# RFRX.net
KiCad netlist of a schematic drawn in Altium Designer
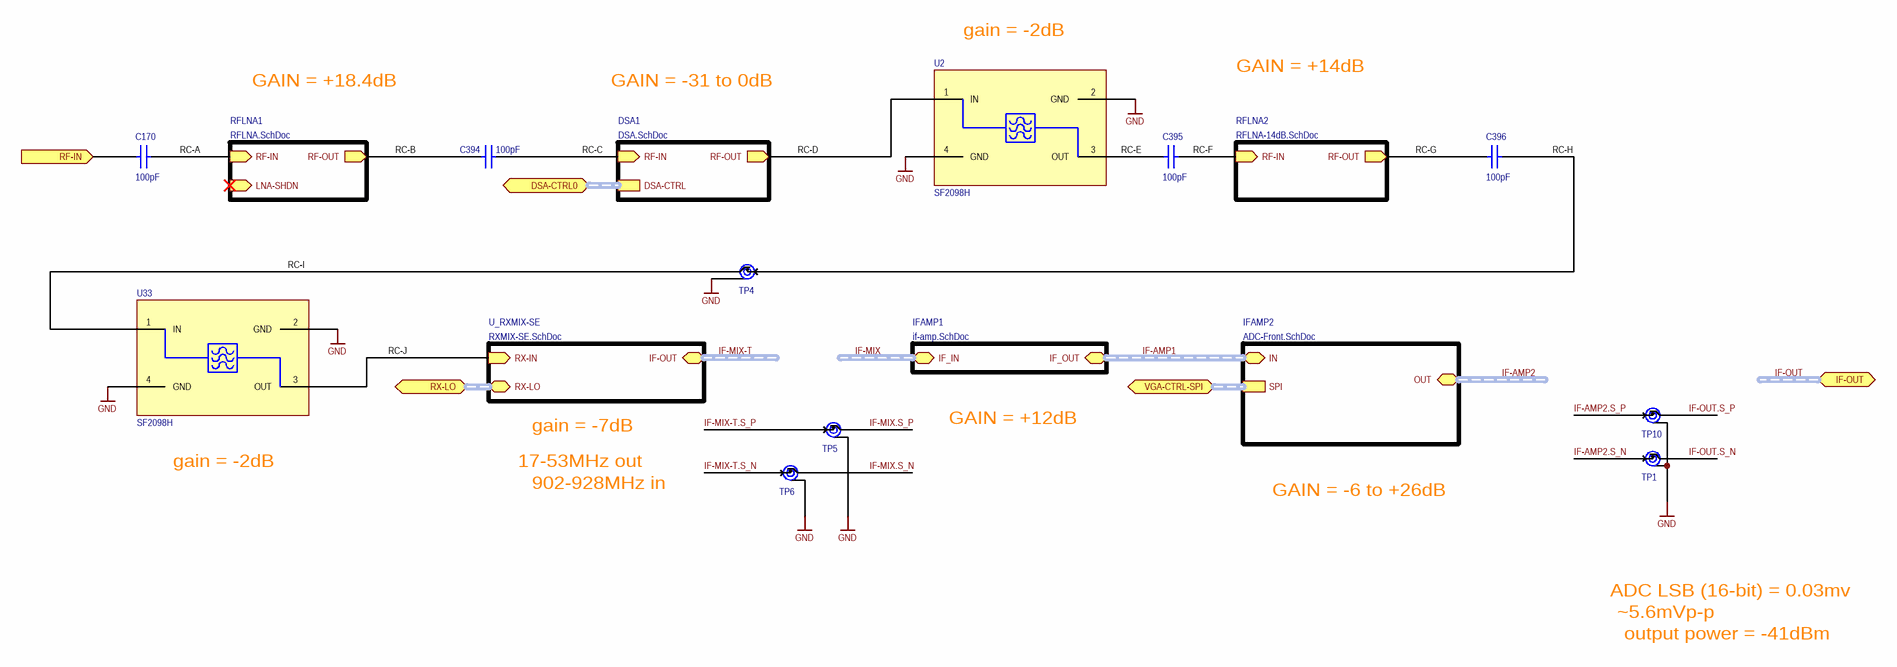
[diagram p0: RFRX.SchDoc]

(export (version "E")
  (design (tool "Eeschema 10.0.6"))
  (components
    (comp (ref "C170")
      (value "100pF")
      (footprint "0402")
      (description "Ceramic Capacitor 100pF ±1% 25V NP0 0402")
      (fields (field (name "VOLTAGE") "25V") (field (name "MANUFACTURER") "Kemet"))
      (libsource (lib "Graviton") (part "CAP 0603"))
    )
    (comp (ref "C394")
      (value "100pF")
      (footprint "0402")
      (description "Ceramic Capacitor 100pF ±1% 25V NP0 0402")
      (fields (field (name "VOLTAGE") "25V") (field (name "MANUFACTURER") "Kemet"))
      (libsource (lib "Graviton") (part "CAP 0603"))
    )
    (comp (ref "C395")
      (value "100pF")
      (footprint "0402")
      (description "Ceramic Capacitor 100pF ±1% 25V NP0 0402")
      (fields (field (name "VOLTAGE") "25V") (field (name "MANUFACTURER") "Kemet"))
      (libsource (lib "Graviton") (part "CAP 0603"))
    )
    (comp (ref "C396")
      (value "100pF")
      (footprint "0402")
      (description "Ceramic Capacitor 100pF ±1% 25V NP0 0402")
      (fields (field (name "VOLTAGE") "25V") (field (name "MANUFACTURER") "Kemet"))
      (libsource (lib "Graviton") (part "CAP 0603"))
    )
    (comp (ref "TP1")
      (value "MS-180(20)")
      (footprint "MS-180(20)")
      (description "Coaxial Connector Switch")
      (fields (field (name "MANUFACTURER") "Hirose"))
      (libsource (lib "hirose") (part "MS-180(20)"))
    )
    (comp (ref "TP4")
      (value "MS-180(20)")
      (footprint "MS-180(20)")
      (description "Coaxial Connector Switch")
      (fields (field (name "MANUFACTURER") "Hirose"))
      (libsource (lib "hirose") (part "MS-180(20)"))
    )
    (comp (ref "TP5")
      (value "MS-180(20)")
      (footprint "MS-180(20)")
      (description "Coaxial Connector Switch")
      (fields (field (name "MANUFACTURER") "Hirose"))
      (libsource (lib "hirose") (part "MS-180(20)"))
    )
    (comp (ref "TP6")
      (value "MS-180(20)")
      (footprint "MS-180(20)")
      (description "Coaxial Connector Switch")
      (fields (field (name "MANUFACTURER") "Hirose"))
      (libsource (lib "hirose") (part "MS-180(20)"))
    )
    (comp (ref "TP10")
      (value "MS-180(20)")
      (footprint "MS-180(20)")
      (description "Coaxial Connector Switch")
      (fields (field (name "MANUFACTURER") "Hirose"))
      (libsource (lib "hirose") (part "MS-180(20)"))
    )
    (comp (ref "U2")
      (value "SF2098H")
      (footprint "rfm:SM2016-4")
      (description "915 MHz SAW Filter")
      (fields (field (name "MANUFACTURER") "RFM"))
      (libsource (lib "rfm") (part "SF2098H"))
    )
    (comp (ref "U33")
      (value "SF2098H")
      (footprint "rfm:SM2016-4")
      (description "915 MHz SAW Filter")
      (fields (field (name "MANUFACTURER") "RFM"))
      (libsource (lib "rfm") (part "SF2098H"))
    )
  )
  (nets
    (net (code "10") (name "/IF-AMP2.S_N") (class "Default")
      (node (ref "TP1") (pin "C") (pinfunction "IN_C") (pintype "passive"))
    )
    (net (code "11") (name "/IF-AMP2.S_P") (class "Default")
      (node (ref "TP10") (pin "C") (pinfunction "IN_C") (pintype "passive"))
    )
    (net (code "12") (name "/IF-MIX-T.S_N") (class "Default")
      (node (ref "TP6") (pin "C") (pinfunction "IN_C") (pintype "passive"))
    )
    (net (code "13") (name "/IF-MIX-T.S_P") (class "Default")
      (node (ref "TP5") (pin "C") (pinfunction "IN_C") (pintype "passive"))
    )
    (net (code "14") (name "/IF-MIX.S_N") (class "Default")
      (node (ref "TP6") (pin "A") (pinfunction "OUT_A") (pintype "passive"))
    )
    (net (code "15") (name "/IF-MIX.S_P") (class "Default")
      (node (ref "TP5") (pin "A") (pinfunction "OUT_A") (pintype "passive"))
    )
    (net (code "16") (name "/IF-OUT.S_N") (class "Default")
      (node (ref "TP1") (pin "A") (pinfunction "OUT_A") (pintype "passive"))
    )
    (net (code "17") (name "/IF-OUT.S_P") (class "Default")
      (node (ref "TP10") (pin "A") (pinfunction "OUT_A") (pintype "passive"))
    )
    (net (code "19") (name "/RC-A") (class "Default")
      (node (ref "C170") (pin "1") (pinfunction "1_1") (pintype "passive"))
    )
    (net (code "20") (name "/RC-B") (class "Default")
      (node (ref "C394") (pin "2") (pinfunction "2_2") (pintype "passive"))
    )
    (net (code "21") (name "/RC-C") (class "Default")
      (node (ref "C394") (pin "1") (pinfunction "1_1") (pintype "passive"))
    )
    (net (code "22") (name "/RC-D") (class "Default")
      (node (ref "U2") (pin "1") (pinfunction "IN_1") (pintype "passive"))
    )
    (net (code "23") (name "/RC-E") (class "Default")
      (node (ref "C395") (pin "2") (pinfunction "2_2") (pintype "passive"))
      (node (ref "U2") (pin "3") (pinfunction "OUT_3") (pintype "passive"))
    )
    (net (code "24") (name "/RC-F") (class "Default")
      (node (ref "C395") (pin "1") (pinfunction "1_1") (pintype "passive"))
    )
    (net (code "25") (name "/RC-G") (class "Default")
      (node (ref "C396") (pin "2") (pinfunction "2_2") (pintype "passive"))
    )
    (net (code "26") (name "/RC-H") (class "Default")
      (node (ref "C396") (pin "1") (pinfunction "1_1") (pintype "passive"))
      (node (ref "TP4") (pin "C") (pinfunction "IN_C") (pintype "passive"))
    )
    (net (code "27") (name "/RC-I") (class "Default")
      (node (ref "TP4") (pin "A") (pinfunction "OUT_A") (pintype "passive"))
      (node (ref "U33") (pin "1") (pinfunction "IN_1") (pintype "passive"))
    )
    (net (code "28") (name "/RC-J") (class "Default")
      (node (ref "U33") (pin "3") (pinfunction "OUT_3") (pintype "passive"))
    )
    (net (code "29") (name "/RF-IN") (class "Default")
      (node (ref "C170") (pin "2") (pinfunction "2_2") (pintype "passive"))
    )
    (net (code "37") (name "GND") (class "Default")
      (node (ref "TP1") (pin "G") (pinfunction "GND_G") (pintype "passive"))
      (node (ref "TP10") (pin "G") (pinfunction "GND_G") (pintype "passive"))
      (node (ref "TP4") (pin "G") (pinfunction "GND_G") (pintype "passive"))
      (node (ref "TP5") (pin "G") (pinfunction "GND_G") (pintype "passive"))
      (node (ref "TP6") (pin "G") (pinfunction "GND_G") (pintype "passive"))
      (node (ref "U2") (pin "2") (pinfunction "GND_2") (pintype "passive"))
      (node (ref "U2") (pin "4") (pinfunction "GND_4") (pintype "passive"))
      (node (ref "U33") (pin "2") (pinfunction "GND_2") (pintype "passive"))
      (node (ref "U33") (pin "4") (pinfunction "GND_4") (pintype "passive"))
    )
  )
)
